# POEInjectorTop.net
KiCad netlist of a schematic drawn in Altium Designer
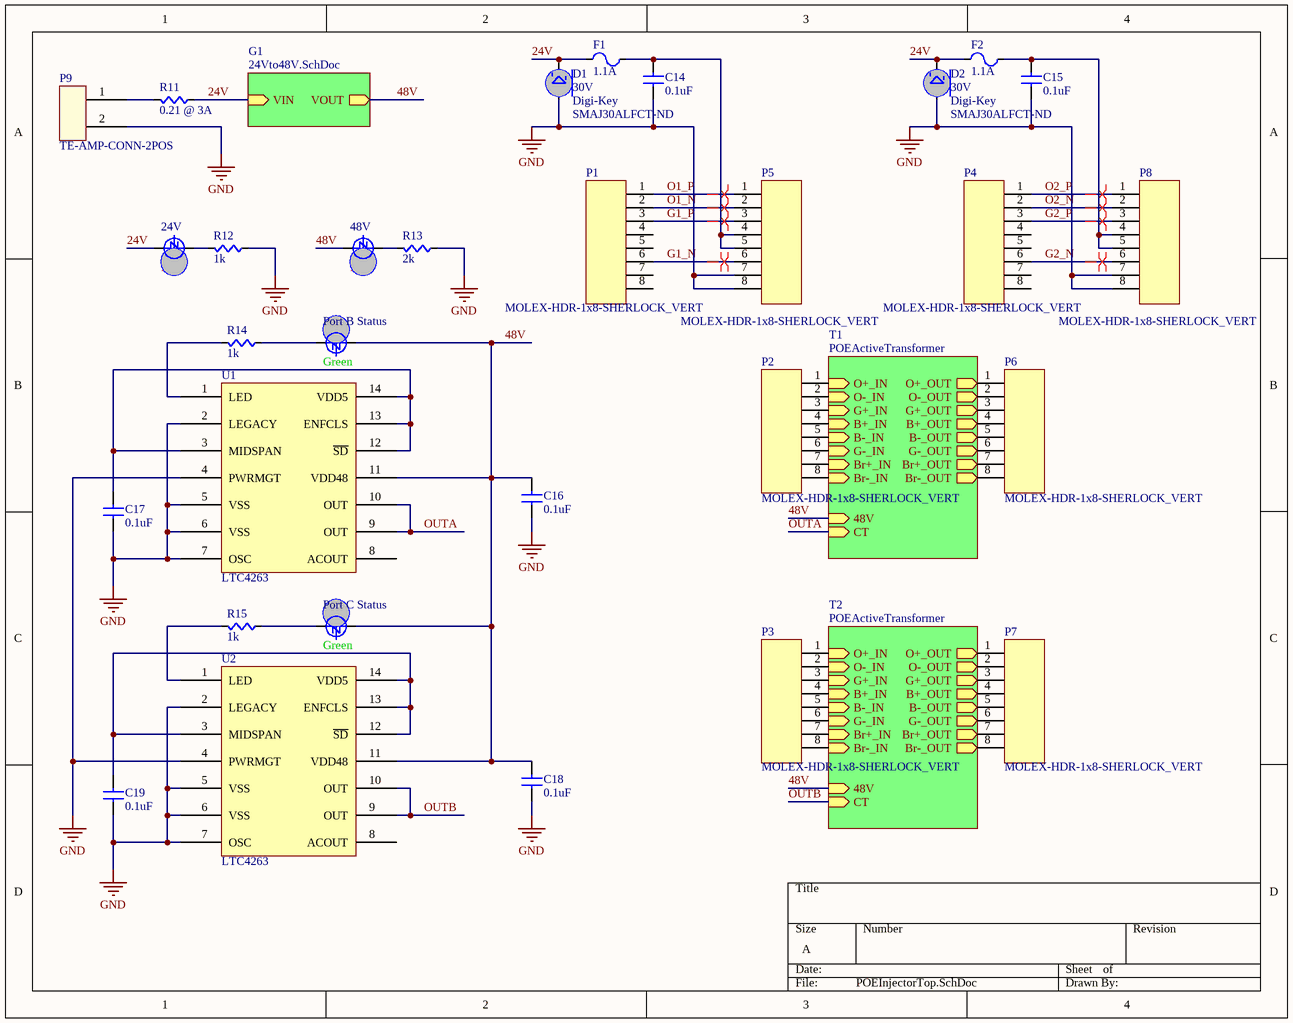
[diagram p0: POEInjectorTop.SchDoc]

(export (version "E")
  (design (tool "Eeschema 10.0.6"))
  (components
    (comp (ref "24V")
      (value "LED")
      (footprint "LED0603")
      (fields (field (name "COLOR") "Red"))
      (libsource (lib "Semiconductors") (part "LED"))
    )
    (comp (ref "48V")
      (value "LED")
      (footprint "LED0603")
      (fields (field (name "COLOR") "Red"))
      (libsource (lib "Semiconductors") (part "LED"))
    )
    (comp (ref "C14")
      (value "0.1uF")
      (footprint "CAPC0603")
      (fields (field (name "Comment") "Cap"))
      (libsource (lib "Passives") (part "Cap"))
    )
    (comp (ref "C15")
      (value "0.1uF")
      (footprint "CAPC0603")
      (fields (field (name "Comment") "Cap"))
      (libsource (lib "Passives") (part "Cap"))
    )
    (comp (ref "C16")
      (value "0.1uF")
      (footprint "CAPC0603")
      (fields (field (name "Comment") "Cap"))
      (libsource (lib "Passives") (part "Cap"))
    )
    (comp (ref "C17")
      (value "0.1uF")
      (footprint "CAPC0603")
      (fields (field (name "Comment") "Cap"))
      (libsource (lib "Passives") (part "Cap"))
    )
    (comp (ref "C18")
      (value "0.1uF")
      (footprint "CAPC0603")
      (fields (field (name "Comment") "Cap"))
      (libsource (lib "Passives") (part "Cap"))
    )
    (comp (ref "C19")
      (value "0.1uF")
      (footprint "CAPC0603")
      (fields (field (name "Comment") "Cap"))
      (libsource (lib "Passives") (part "Cap"))
    )
    (comp (ref "D1")
      (value "30V")
      (footprint "SMASeries")
      (description "Zener Diode")
      (fields
        (field (name "SUPPLIER 1") "Digi-Key")
        (field (name "SUPPLIER PART NUMBER 1") "SMAJ30ALFCT-ND")
        (field (name "Comment") "Zener")
      )
      (libsource (lib "Semiconductors") (part "Zener"))
    )
    (comp (ref "D2")
      (value "30V")
      (footprint "SMASeries")
      (description "Zener Diode")
      (fields
        (field (name "SUPPLIER 1") "Digi-Key")
        (field (name "SUPPLIER PART NUMBER 1") "SMAJ30ALFCT-ND")
        (field (name "Comment") "Zener")
      )
      (libsource (lib "Semiconductors") (part "Zener"))
    )
    (comp (ref "F1")
      (value "1.1A")
      (footprint "PTC7451X11N")
      (fields (field (name "Comment") "PTC Fuse"))
      (libsource (lib "Passives") (part "PTC_Fuse"))
    )
    (comp (ref "F2")
      (value "1.1A")
      (footprint "PTC7451X11N")
      (fields (field (name "Comment") "PTC Fuse"))
      (libsource (lib "Passives") (part "PTC_Fuse"))
    )
    (comp (ref "P1")
      (value "MOLEX-HDR-1x8-SHERLOCK_VERT")
      (footprint "Connectors:MOLEX-HDR-1X8-SHERLOCK-VERT")
      (description "CONN HEADER 8POS 2MM VERT TIN")
      (libsource (lib "Connectors") (part "MOLEX-HDR-1x8-SHERLOCK_VERT"))
    )
    (comp (ref "P2")
      (value "MOLEX-HDR-1x8-SHERLOCK_VERT")
      (footprint "Connectors:MOLEX-HDR-1X8-SHERLOCK-VERT")
      (description "CONN HEADER 8POS 2MM VERT TIN")
      (libsource (lib "Connectors") (part "MOLEX-HDR-1x8-SHERLOCK_VERT"))
    )
    (comp (ref "P3")
      (value "MOLEX-HDR-1x8-SHERLOCK_VERT")
      (footprint "Connectors:MOLEX-HDR-1X8-SHERLOCK-VERT")
      (description "CONN HEADER 8POS 2MM VERT TIN")
      (libsource (lib "Connectors") (part "MOLEX-HDR-1x8-SHERLOCK_VERT"))
    )
    (comp (ref "P4")
      (value "MOLEX-HDR-1x8-SHERLOCK_VERT")
      (footprint "Connectors:MOLEX-HDR-1X8-SHERLOCK-VERT")
      (description "CONN HEADER 8POS 2MM VERT TIN")
      (libsource (lib "Connectors") (part "MOLEX-HDR-1x8-SHERLOCK_VERT"))
    )
    (comp (ref "P5")
      (value "MOLEX-HDR-1x8-SHERLOCK_VERT")
      (footprint "Connectors:MOLEX-HDR-1X8-SHERLOCK-VERT")
      (description "CONN HEADER 8POS 2MM VERT TIN")
      (libsource (lib "") (part "MOLEX-HDR-1x8-SHERLOCK_VERT_1"))
    )
    (comp (ref "P6")
      (value "MOLEX-HDR-1x8-SHERLOCK_VERT")
      (footprint "Connectors:MOLEX-HDR-1X8-SHERLOCK-VERT")
      (description "CONN HEADER 8POS 2MM VERT TIN")
      (libsource (lib "") (part "MOLEX-HDR-1x8-SHERLOCK_VERT_1"))
    )
    (comp (ref "P7")
      (value "MOLEX-HDR-1x8-SHERLOCK_VERT")
      (footprint "Connectors:MOLEX-HDR-1X8-SHERLOCK-VERT")
      (description "CONN HEADER 8POS 2MM VERT TIN")
      (libsource (lib "") (part "MOLEX-HDR-1x8-SHERLOCK_VERT_1"))
    )
    (comp (ref "P8")
      (value "MOLEX-HDR-1x8-SHERLOCK_VERT")
      (footprint "Connectors:MOLEX-HDR-1X8-SHERLOCK-VERT")
      (description "CONN HEADER 8POS 2MM VERT TIN")
      (libsource (lib "") (part "MOLEX-HDR-1x8-SHERLOCK_VERT_1"))
    )
    (comp (ref "P9")
      (value "TE-AMP-CONN-2POS")
      (footprint "Connectors:TE AMP CONN 2POS")
      (description "2 Positions Header Connector 0.156\" (3.96mm) Through Hole Tin")
      (libsource (lib "Connectors") (part "TE-AMP-CONN-2POS"))
    )
    (comp (ref "Port B Status")
      (value "LED")
      (footprint "LED0603")
      (fields (field (name "COLOR") "Green"))
      (libsource (lib "") (part "LED_1"))
    )
    (comp (ref "Port C Status")
      (value "LED")
      (footprint "LED0603")
      (fields (field (name "COLOR") "Green"))
      (libsource (lib "") (part "LED_1"))
    )
    (comp (ref "R11")
      (value "0.21 @ 3A")
      (footprint "Miscellaneous Devices:AXIAL-0.3")
      (fields (field (name "Comment") "Res"))
      (libsource (lib "Passives") (part "Res"))
    )
    (comp (ref "R12")
      (value "1k")
      (footprint "RES0603")
      (fields (field (name "Comment") "Res"))
      (libsource (lib "Passives") (part "Res"))
    )
    (comp (ref "R13")
      (value "2k")
      (footprint "RES0603")
      (fields (field (name "Comment") "Res"))
      (libsource (lib "Passives") (part "Res"))
    )
    (comp (ref "R14")
      (value "1k")
      (footprint "RES0603")
      (fields (field (name "Comment") "Res"))
      (libsource (lib "Passives") (part "Res"))
    )
    (comp (ref "R15")
      (value "1k")
      (footprint "RES0603")
      (fields (field (name "Comment") "Res"))
      (libsource (lib "Passives") (part "Res"))
    )
    (comp (ref "U1")
      (value "LTC4263")
      (footprint "LTC4263")
      (description "IC POE 803.2AF SINGL PSE 14-SOIC")
      (libsource (lib "ICs") (part "LTC4263"))
    )
    (comp (ref "U2")
      (value "LTC4263")
      (footprint "LTC4263")
      (description "IC POE 803.2AF SINGL PSE 14-SOIC")
      (libsource (lib "ICs") (part "LTC4263"))
    )
  )
  (nets
    (net (code "1") (name "/24V") (class "Default")
      (node (ref "24V") (pin "A") (pinfunction "A_A") (pintype "passive"))
      (node (ref "D1") (pin "C") (pinfunction "C_C") (pintype "passive"))
      (node (ref "D2") (pin "C") (pinfunction "C_C") (pintype "passive"))
      (node (ref "F1") (pin "1") (pinfunction "A_1") (pintype "passive"))
      (node (ref "F2") (pin "1") (pinfunction "A_1") (pintype "passive"))
      (node (ref "R11") (pin "2") (pinfunction "B_2") (pintype "passive"))
    )
    (net (code "2") (name "/48V") (class "Default")
      (node (ref "48V") (pin "A") (pinfunction "A_A") (pintype "passive"))
      (node (ref "C16") (pin "1") (pinfunction "A_1") (pintype "passive"))
      (node (ref "C18") (pin "1") (pinfunction "A_1") (pintype "passive"))
      (node (ref "Port B Status") (pin "A") (pinfunction "A_A") (pintype "passive"))
      (node (ref "Port C Status") (pin "A") (pinfunction "A_A") (pintype "passive"))
      (node (ref "U1") (pin "11") (pinfunction "VDD48_11") (pintype "passive"))
      (node (ref "U2") (pin "11") (pinfunction "VDD48_11") (pintype "passive"))
    )
    (net (code "3") (name "/B+_IN") (class "Default")
      (node (ref "P3") (pin "4") (pinfunction "4_4") (pintype "passive"))
    )
    (net (code "4") (name "/B+_IN_1") (class "Default")
      (node (ref "P2") (pin "4") (pinfunction "4_4") (pintype "passive"))
    )
    (net (code "5") (name "/B+_OUT") (class "Default")
      (node (ref "P7") (pin "4") (pinfunction "4_4") (pintype "passive"))
    )
    (net (code "6") (name "/B+_OUT_1") (class "Default")
      (node (ref "P6") (pin "4") (pinfunction "4_4") (pintype "passive"))
    )
    (net (code "7") (name "/B-_IN") (class "Default")
      (node (ref "P3") (pin "5") (pinfunction "5_5") (pintype "passive"))
    )
    (net (code "8") (name "/B-_IN_1") (class "Default")
      (node (ref "P2") (pin "5") (pinfunction "5_5") (pintype "passive"))
    )
    (net (code "9") (name "/B-_OUT") (class "Default")
      (node (ref "P7") (pin "5") (pinfunction "5_5") (pintype "passive"))
    )
    (net (code "10") (name "/B-_OUT_1") (class "Default")
      (node (ref "P6") (pin "5") (pinfunction "5_5") (pintype "passive"))
    )
    (net (code "11") (name "/Br+_IN") (class "Default")
      (node (ref "P3") (pin "7") (pinfunction "7_7") (pintype "passive"))
    )
    (net (code "12") (name "/Br+_IN_1") (class "Default")
      (node (ref "P2") (pin "7") (pinfunction "7_7") (pintype "passive"))
    )
    (net (code "13") (name "/Br+_OUT") (class "Default")
      (node (ref "P7") (pin "7") (pinfunction "7_7") (pintype "passive"))
    )
    (net (code "14") (name "/Br+_OUT_1") (class "Default")
      (node (ref "P6") (pin "7") (pinfunction "7_7") (pintype "passive"))
    )
    (net (code "15") (name "/Br-_IN") (class "Default")
      (node (ref "P3") (pin "8") (pinfunction "8_8") (pintype "passive"))
    )
    (net (code "16") (name "/Br-_IN_1") (class "Default")
      (node (ref "P2") (pin "8") (pinfunction "8_8") (pintype "passive"))
    )
    (net (code "17") (name "/Br-_OUT") (class "Default")
      (node (ref "P7") (pin "8") (pinfunction "8_8") (pintype "passive"))
    )
    (net (code "18") (name "/Br-_OUT_1") (class "Default")
      (node (ref "P6") (pin "8") (pinfunction "8_8") (pintype "passive"))
    )
    (net (code "19") (name "/G+_IN") (class "Default")
      (node (ref "P3") (pin "3") (pinfunction "3_3") (pintype "passive"))
    )
    (net (code "20") (name "/G+_IN_1") (class "Default")
      (node (ref "P2") (pin "3") (pinfunction "3_3") (pintype "passive"))
    )
    (net (code "21") (name "/G+_OUT") (class "Default")
      (node (ref "P7") (pin "3") (pinfunction "3_3") (pintype "passive"))
    )
    (net (code "22") (name "/G+_OUT_1") (class "Default")
      (node (ref "P6") (pin "3") (pinfunction "3_3") (pintype "passive"))
    )
    (net (code "23") (name "/G-_IN") (class "Default")
      (node (ref "P3") (pin "6") (pinfunction "6_6") (pintype "passive"))
    )
    (net (code "24") (name "/G-_IN_1") (class "Default")
      (node (ref "P2") (pin "6") (pinfunction "6_6") (pintype "passive"))
    )
    (net (code "25") (name "/G-_OUT") (class "Default")
      (node (ref "P7") (pin "6") (pinfunction "6_6") (pintype "passive"))
    )
    (net (code "26") (name "/G-_OUT_1") (class "Default")
      (node (ref "P6") (pin "6") (pinfunction "6_6") (pintype "passive"))
    )
    (net (code "27") (name "/G1_N") (class "Default")
      (node (ref "P1") (pin "6") (pinfunction "6_6") (pintype "passive"))
      (node (ref "P5") (pin "6") (pinfunction "6_6") (pintype "passive"))
    )
    (net (code "28") (name "/G1_P") (class "Default")
      (node (ref "P1") (pin "3") (pinfunction "3_3") (pintype "passive"))
      (node (ref "P5") (pin "3") (pinfunction "3_3") (pintype "passive"))
    )
    (net (code "29") (name "/G2_N") (class "Default")
      (node (ref "P4") (pin "6") (pinfunction "6_6") (pintype "passive"))
      (node (ref "P8") (pin "6") (pinfunction "6_6") (pintype "passive"))
    )
    (net (code "30") (name "/G2_P") (class "Default")
      (node (ref "P4") (pin "3") (pinfunction "3_3") (pintype "passive"))
      (node (ref "P8") (pin "3") (pinfunction "3_3") (pintype "passive"))
    )
    (net (code "31") (name "/O+_IN") (class "Default")
      (node (ref "P3") (pin "1") (pinfunction "1_1") (pintype "passive"))
    )
    (net (code "32") (name "/O+_IN_1") (class "Default")
      (node (ref "P2") (pin "1") (pinfunction "1_1") (pintype "passive"))
    )
    (net (code "33") (name "/O+_OUT") (class "Default")
      (node (ref "P7") (pin "1") (pinfunction "1_1") (pintype "passive"))
    )
    (net (code "34") (name "/O+_OUT_1") (class "Default")
      (node (ref "P6") (pin "1") (pinfunction "1_1") (pintype "passive"))
    )
    (net (code "35") (name "/O-_IN") (class "Default")
      (node (ref "P3") (pin "2") (pinfunction "2_2") (pintype "passive"))
    )
    (net (code "36") (name "/O-_IN_1") (class "Default")
      (node (ref "P2") (pin "2") (pinfunction "2_2") (pintype "passive"))
    )
    (net (code "37") (name "/O-_OUT") (class "Default")
      (node (ref "P7") (pin "2") (pinfunction "2_2") (pintype "passive"))
    )
    (net (code "38") (name "/O-_OUT_1") (class "Default")
      (node (ref "P6") (pin "2") (pinfunction "2_2") (pintype "passive"))
    )
    (net (code "39") (name "/O1_N") (class "Default")
      (node (ref "P1") (pin "2") (pinfunction "2_2") (pintype "passive"))
      (node (ref "P5") (pin "2") (pinfunction "2_2") (pintype "passive"))
    )
    (net (code "40") (name "/O1_P") (class "Default")
      (node (ref "P1") (pin "1") (pinfunction "1_1") (pintype "passive"))
      (node (ref "P5") (pin "1") (pinfunction "1_1") (pintype "passive"))
    )
    (net (code "41") (name "/O2_N") (class "Default")
      (node (ref "P4") (pin "2") (pinfunction "2_2") (pintype "passive"))
      (node (ref "P8") (pin "2") (pinfunction "2_2") (pintype "passive"))
    )
    (net (code "42") (name "/O2_P") (class "Default")
      (node (ref "P4") (pin "1") (pinfunction "1_1") (pintype "passive"))
      (node (ref "P8") (pin "1") (pinfunction "1_1") (pintype "passive"))
    )
    (net (code "43") (name "/OUTA") (class "Default")
      (node (ref "U1") (pin "10") (pinfunction "OUT_10") (pintype "passive"))
      (node (ref "U1") (pin "9") (pinfunction "OUT_9") (pintype "passive"))
    )
    (net (code "44") (name "/OUTB") (class "Default")
      (node (ref "U2") (pin "10") (pinfunction "OUT_10") (pintype "passive"))
      (node (ref "U2") (pin "9") (pinfunction "OUT_9") (pintype "passive"))
    )
    (net (code "45") (name "GND") (class "Default")
      (node (ref "C14") (pin "2") (pinfunction "B_2") (pintype "passive"))
      (node (ref "C15") (pin "2") (pinfunction "B_2") (pintype "passive"))
      (node (ref "C16") (pin "2") (pinfunction "B_2") (pintype "passive"))
      (node (ref "C17") (pin "2") (pinfunction "B_2") (pintype "passive"))
      (node (ref "C18") (pin "2") (pinfunction "B_2") (pintype "passive"))
      (node (ref "C19") (pin "2") (pinfunction "B_2") (pintype "passive"))
      (node (ref "D1") (pin "A") (pinfunction "A_A") (pintype "passive"))
      (node (ref "D2") (pin "A") (pinfunction "A_A") (pintype "passive"))
      (node (ref "P5") (pin "7") (pinfunction "7_7") (pintype "passive"))
      (node (ref "P5") (pin "8") (pinfunction "8_8") (pintype "passive"))
      (node (ref "P8") (pin "7") (pinfunction "7_7") (pintype "passive"))
      (node (ref "P8") (pin "8") (pinfunction "8_8") (pintype "passive"))
      (node (ref "P9") (pin "2") (pinfunction "2_2") (pintype "passive"))
      (node (ref "R12") (pin "2") (pinfunction "B_2") (pintype "passive"))
      (node (ref "R13") (pin "2") (pinfunction "B_2") (pintype "passive"))
      (node (ref "U1") (pin "2") (pinfunction "LEGACY_2") (pintype "passive"))
      (node (ref "U1") (pin "4") (pinfunction "PWRMGT_4") (pintype "passive"))
      (node (ref "U1") (pin "5") (pinfunction "VSS_5") (pintype "passive"))
      (node (ref "U1") (pin "6") (pinfunction "VSS_6") (pintype "passive"))
      (node (ref "U1") (pin "7") (pinfunction "OSC_7") (pintype "passive"))
      (node (ref "U2") (pin "2") (pinfunction "LEGACY_2") (pintype "passive"))
      (node (ref "U2") (pin "4") (pinfunction "PWRMGT_4") (pintype "passive"))
      (node (ref "U2") (pin "5") (pinfunction "VSS_5") (pintype "passive"))
      (node (ref "U2") (pin "6") (pinfunction "VSS_6") (pintype "passive"))
      (node (ref "U2") (pin "7") (pinfunction "OSC_7") (pintype "passive"))
    )
    (net (code "46") (name "Net-(C14-A)") (class "Default")
      (node (ref "C14") (pin "1") (pinfunction "A_1") (pintype "passive"))
      (node (ref "F1") (pin "2") (pinfunction "B_2") (pintype "passive"))
      (node (ref "P5") (pin "4") (pinfunction "4_4") (pintype "passive"))
      (node (ref "P5") (pin "5") (pinfunction "5_5") (pintype "passive"))
    )
    (net (code "47") (name "Net-(C15-A)") (class "Default")
      (node (ref "C15") (pin "1") (pinfunction "A_1") (pintype "passive"))
      (node (ref "F2") (pin "2") (pinfunction "B_2") (pintype "passive"))
      (node (ref "P8") (pin "4") (pinfunction "4_4") (pintype "passive"))
      (node (ref "P8") (pin "5") (pinfunction "5_5") (pintype "passive"))
    )
    (net (code "48") (name "Net-(C17-A)") (class "Default")
      (node (ref "C17") (pin "1") (pinfunction "A_1") (pintype "passive"))
      (node (ref "U1") (pin "12") (pinfunction "~{SD}_12") (pintype "passive"))
      (node (ref "U1") (pin "13") (pinfunction "ENFCLS_13") (pintype "passive"))
      (node (ref "U1") (pin "14") (pinfunction "VDD5_14") (pintype "passive"))
      (node (ref "U1") (pin "3") (pinfunction "MIDSPAN_3") (pintype "passive"))
    )
    (net (code "49") (name "Net-(C19-A)") (class "Default")
      (node (ref "C19") (pin "1") (pinfunction "A_1") (pintype "passive"))
      (node (ref "U2") (pin "12") (pinfunction "~{SD}_12") (pintype "passive"))
      (node (ref "U2") (pin "13") (pinfunction "ENFCLS_13") (pintype "passive"))
      (node (ref "U2") (pin "14") (pinfunction "VDD5_14") (pintype "passive"))
      (node (ref "U2") (pin "3") (pinfunction "MIDSPAN_3") (pintype "passive"))
    )
    (net (code "50") (name "Net-(R11-A)") (class "Default")
      (node (ref "P9") (pin "1") (pinfunction "1_1") (pintype "passive"))
      (node (ref "R11") (pin "1") (pinfunction "A_1") (pintype "passive"))
    )
    (net (code "51") (name "Net-(R12-A)") (class "Default")
      (node (ref "24V") (pin "C") (pinfunction "C_C") (pintype "passive"))
      (node (ref "R12") (pin "1") (pinfunction "A_1") (pintype "passive"))
    )
    (net (code "52") (name "Net-(R13-A)") (class "Default")
      (node (ref "48V") (pin "C") (pinfunction "C_C") (pintype "passive"))
      (node (ref "R13") (pin "1") (pinfunction "A_1") (pintype "passive"))
    )
    (net (code "53") (name "Net-(R14-A)") (class "Default")
      (node (ref "R14") (pin "1") (pinfunction "A_1") (pintype "passive"))
      (node (ref "U1") (pin "1") (pinfunction "LED_1") (pintype "passive"))
    )
    (net (code "54") (name "Net-(R14-B)") (class "Default")
      (node (ref "Port B Status") (pin "C") (pinfunction "C_C") (pintype "passive"))
      (node (ref "R14") (pin "2") (pinfunction "B_2") (pintype "passive"))
    )
    (net (code "55") (name "Net-(R15-A)") (class "Default")
      (node (ref "R15") (pin "1") (pinfunction "A_1") (pintype "passive"))
      (node (ref "U2") (pin "1") (pinfunction "LED_1") (pintype "passive"))
    )
    (net (code "56") (name "Net-(R15-B)") (class "Default")
      (node (ref "Port C Status") (pin "C") (pinfunction "C_C") (pintype "passive"))
      (node (ref "R15") (pin "2") (pinfunction "B_2") (pintype "passive"))
    )
    (net (code "57") (name "unconnected-(P1-Pad4)") (class "Default")
      (node (ref "P1") (pin "4") (pinfunction "4_4") (pintype "passive"))
    )
    (net (code "58") (name "unconnected-(P1-Pad5)") (class "Default")
      (node (ref "P1") (pin "5") (pinfunction "5_5") (pintype "passive"))
    )
    (net (code "59") (name "unconnected-(P1-Pad7)") (class "Default")
      (node (ref "P1") (pin "7") (pinfunction "7_7") (pintype "passive"))
    )
    (net (code "60") (name "unconnected-(P1-Pad8)") (class "Default")
      (node (ref "P1") (pin "8") (pinfunction "8_8") (pintype "passive"))
    )
    (net (code "61") (name "unconnected-(P4-Pad4)") (class "Default")
      (node (ref "P4") (pin "4") (pinfunction "4_4") (pintype "passive"))
    )
    (net (code "62") (name "unconnected-(P4-Pad5)") (class "Default")
      (node (ref "P4") (pin "5") (pinfunction "5_5") (pintype "passive"))
    )
    (net (code "63") (name "unconnected-(P4-Pad7)") (class "Default")
      (node (ref "P4") (pin "7") (pinfunction "7_7") (pintype "passive"))
    )
    (net (code "64") (name "unconnected-(P4-Pad8)") (class "Default")
      (node (ref "P4") (pin "8") (pinfunction "8_8") (pintype "passive"))
    )
    (net (code "65") (name "unconnected-(U1-ACOUT-Pad8)") (class "Default")
      (node (ref "U1") (pin "8") (pinfunction "ACOUT_8") (pintype "passive"))
    )
    (net (code "66") (name "unconnected-(U2-ACOUT-Pad8)") (class "Default")
      (node (ref "U2") (pin "8") (pinfunction "ACOUT_8") (pintype "passive"))
    )
  )
)
